# Beetech_Metro_Shield_1_1.net
KiCad netlist of a schematic drawn in Altium Designer
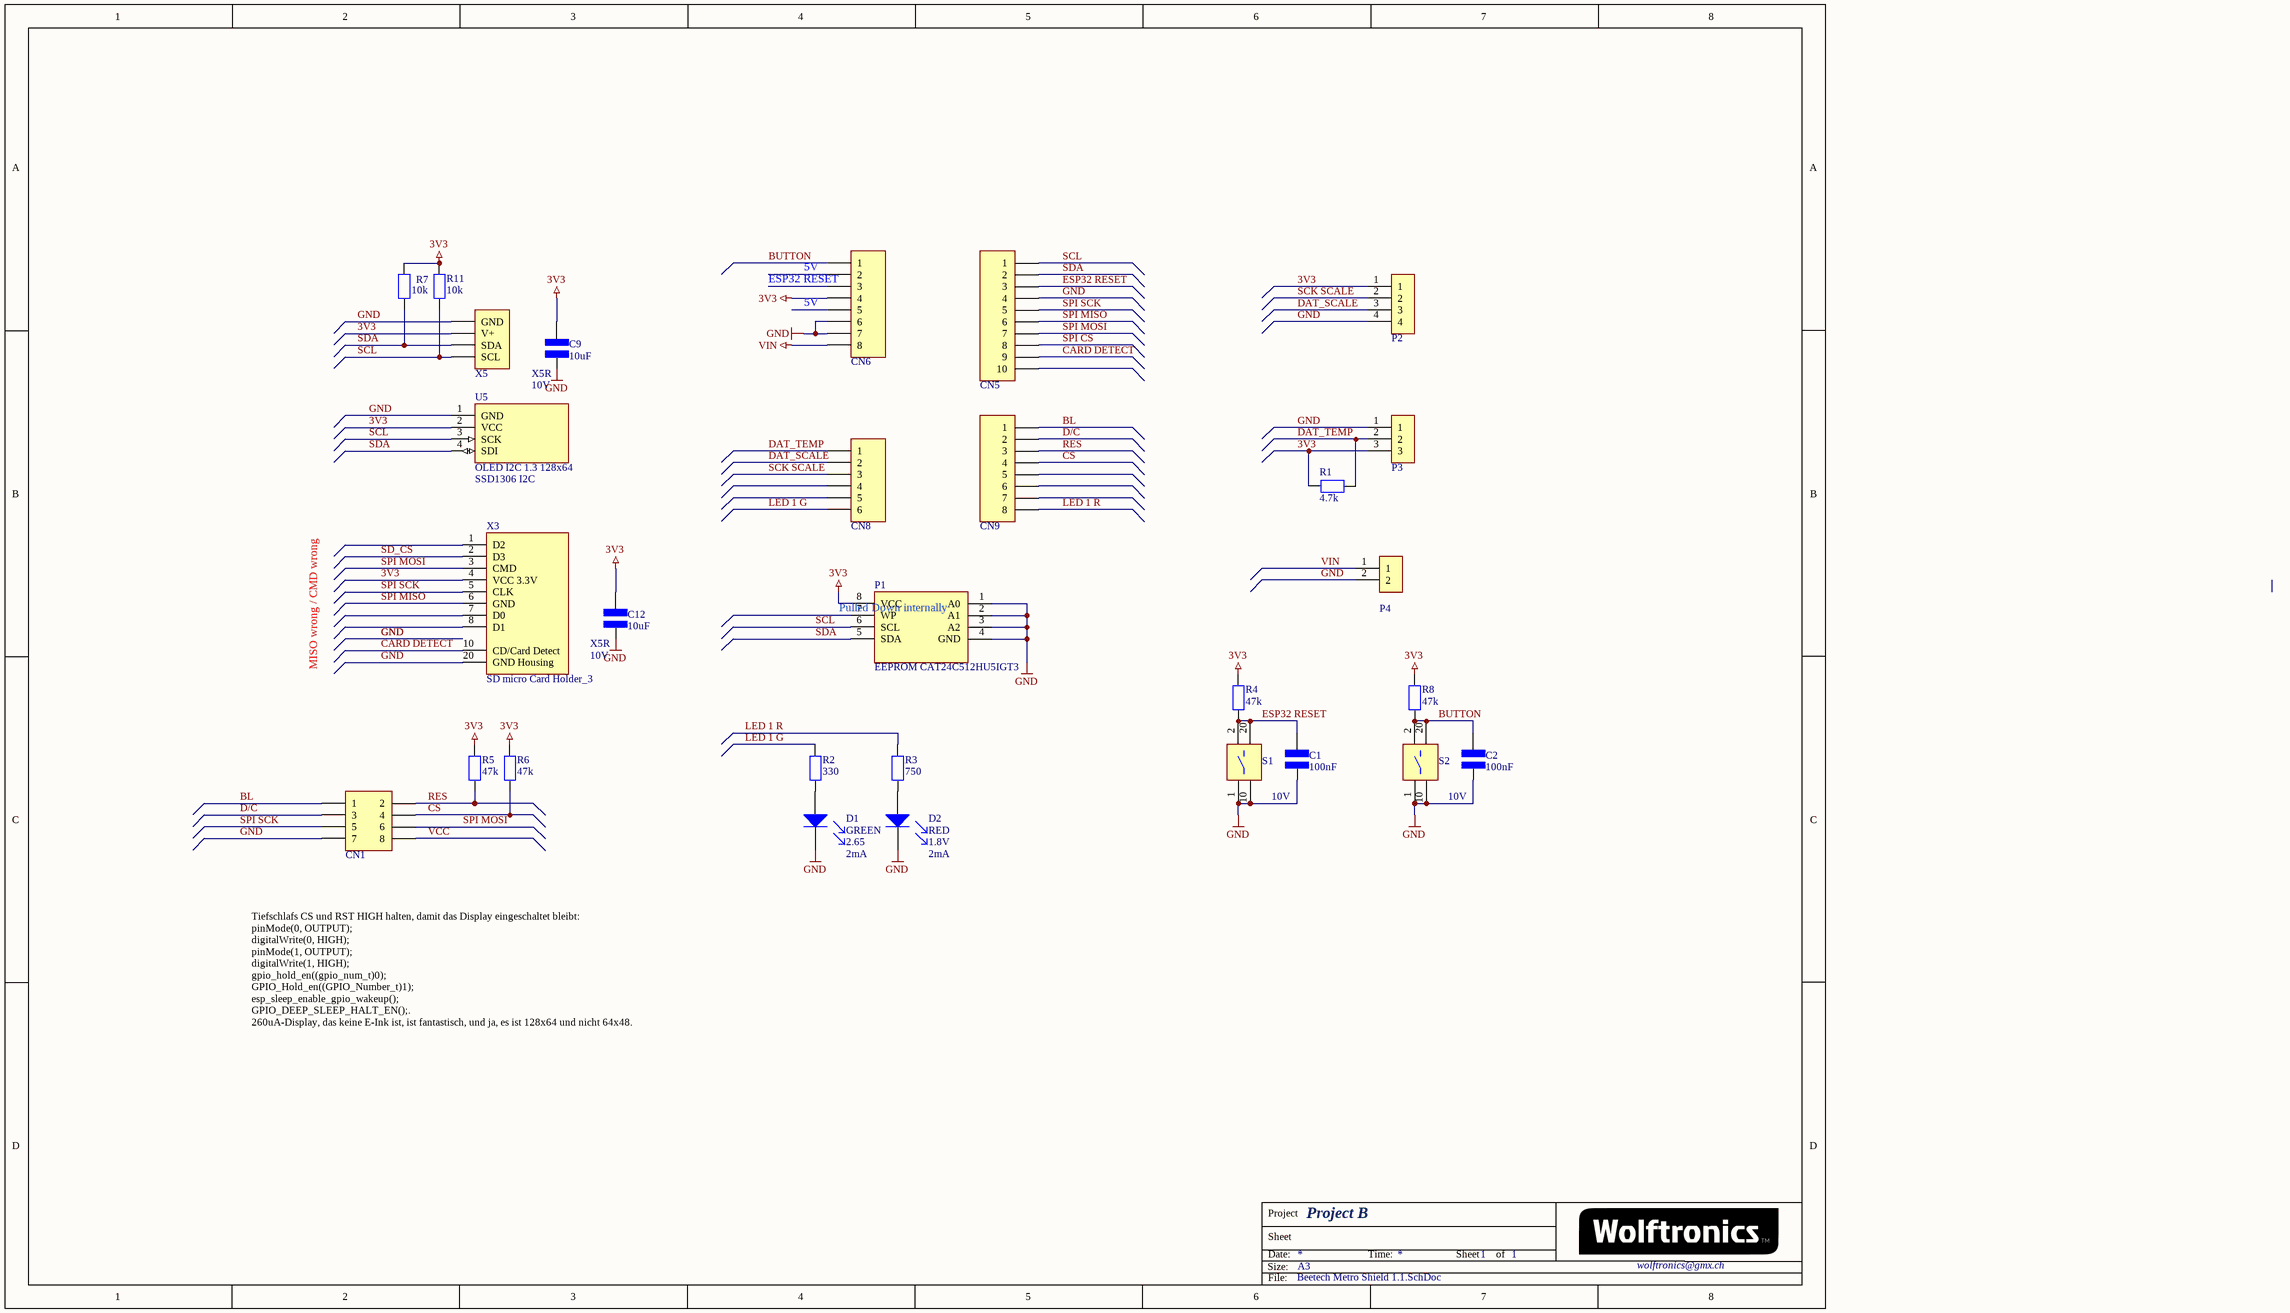
[diagram p0: Beetech Metro Shield 1.1.SchDoc]

(export (version "E")
  (design (tool "Eeschema 10.0.6"))
  (components
    (comp (ref "C1")
      (value "100nF")
      (footprint "CAP 0603 - OUTLINE")
      (description "C CERAMIC SMD")
      (fields (field (name "UMAX") "10V") (field (name "Comment") "100nF 0603"))
      (libsource (lib "Library CAP") (part "100nF 0603"))
    )
    (comp (ref "C2")
      (value "100nF")
      (footprint "CAP 0603 - OUTLINE")
      (description "C CERAMIC SMD")
      (fields (field (name "UMAX") "10V") (field (name "Comment") "100nF 0603"))
      (libsource (lib "Library CAP") (part "100nF 0603"))
    )
    (comp (ref "C9")
      (value "10uF")
      (footprint "CAP 0603 - OUTLINE")
      (description "C CERAMIC SMD")
      (fields
        (field (name "UMAX") "10V")
        (field (name "DIELEKTRIKUM") "X5R")
        (field (name "Comment") "10uF 0603")
      )
      (libsource (lib "Library CAP") (part "10uF 0603"))
    )
    (comp (ref "C12")
      (value "10uF")
      (footprint "CAP 0603 - OUTLINE")
      (description "C CERAMIC SMD")
      (fields
        (field (name "UMAX") "10V")
        (field (name "DIELEKTRIKUM") "X5R")
        (field (name "Comment") "10uF 0603")
      )
      (libsource (lib "Library CAP") (part "10uF 0603"))
    )
    (comp (ref "CN1")
      (value "4 X 2  Header")
      (footprint "4 x 2 2.54mm - no Connector")
      (libsource (lib "Library Scematic") (part "4 X 2  Header"))
    )
    (comp (ref "CN5")
      (value "10-Pin Stiftleiste 10x1 2.54 Low Profile")
      (footprint "10PIN - III")
      (description "Low Profile 10-Pin Stiftleiste 10x1 2.54 Low Profile")
      (libsource (lib "Library Scematic") (part "10-Pin Stiftleiste 10x1 2.54 Low Profile"))
    )
    (comp (ref "CN6")
      (value "8-Pin Stiftleiste 8x1 2.54 Low Profile")
      (footprint "8 PIN - Stiftleiste")
      (description "Low Profile 8-Pin Stiftleiste 8x1 2.54")
      (libsource (lib "") (part "8-Pin Stiftleiste 8x1 2.54 Low Profile_1"))
    )
    (comp (ref "CN8")
      (value "6-PiN")
      (footprint "6PIN")
      (description "6-Pin")
      (fields (field (name "PUBLISHER") "Altium Limited"))
      (libsource (lib "Library Scematic") (part "6-PiN"))
    )
    (comp (ref "CN9")
      (value "8-Pin Stiftleiste 8x1 2.54 Low Profile")
      (footprint "8 PIN - Stiftleiste")
      (description "Low Profile 8-Pin Stiftleiste 8x1 2.54")
      (libsource (lib "Library Scematic") (part "8-Pin Stiftleiste 8x1 2.54 Low Profile"))
    )
    (comp (ref "D1")
      (value "LED Diode SMD LOW CURRENT")
      (footprint "LED SMD 0603 FOOTPRINT")
      (description "LED Green APT1608LZGCK")
      (fields
        (field (name "COLOR") "GREEN")
        (field (name "FORWARD VOLTAGE") "2.65")
        (field (name "IF") "2mA")
      )
      (libsource (lib "Library DIODE") (part "LED Diode SMD - GREEN - 0603 - 2mA_1"))
    )
    (comp (ref "D2")
      (value "LED Diode SMD LOW CURRENT")
      (footprint "LED SMD 0603 FOOTPRINT")
      (description "LED Red APT1608LSECKJ3RV")
      (fields (field (name "COLOR") "RED") (field (name "FORWARD VOLTAGE") "1.8V") (field (name "IF") "2mA"))
      (libsource (lib "Library DIODE") (part "LED Diode SMD - RED - 0603 - 2mA_1"))
    )
    (comp (ref "P1")
      (value "EEPROM CAT24C512HU5IGT3")
      (footprint "UDFN8 3.0x2.0 CAT24C512HU5IGT3")
      (libsource (lib "Library Scematic") (part "EEPROM CAT24C512HU5IGT3"))
    )
    (comp (ref "P2")
      (value "4-Pin Right Angle Housing")
      (footprint "4PIN - RND 205-EK254-2.54-04P")
      (description "4-Pin")
      (libsource (lib "Library Scematic") (part "4-Pin Screw Terminal"))
    )
    (comp (ref "P3")
      (value "3-Pin Right Angle Housing")
      (footprint "3PIN - RND 205-EK254-2.54-03P")
      (description "3-Pin")
      (libsource (lib "Library Scematic") (part "3-Pin Screw Terminal"))
    )
    (comp (ref "P4")
      (value "2-Pin Right Angle Housing")
      (footprint "2PIN - RND 205-EK254-2.54-02P")
      (description "2-Pin")
      (libsource (lib "Library Scematic") (part "2-Pin Screw Terminal"))
    )
    (comp (ref "R1")
      (value "4.7k")
      (footprint "RES 0603 FOOTPRINT - OUTLINE")
      (description "R SMD")
      (fields (field (name "Comment") "4.7k Ohm 0603"))
      (libsource (lib "Library RES") (part "4.7k Ohm 0603"))
    )
    (comp (ref "R2")
      (value "330")
      (footprint "RES 0603 FOOTPRINT - OUTLINE")
      (description "R SMD")
      (fields (field (name "Comment") "330 Ohm 0603"))
      (libsource (lib "Library RES") (part "330 Ohm 0603"))
    )
    (comp (ref "R3")
      (value "750")
      (footprint "RES 0603 FOOTPRINT - OUTLINE")
      (description "R SMD")
      (fields (field (name "Comment") "750 Ohm 0603"))
      (libsource (lib "Library RES") (part "750 Ohm 0603"))
    )
    (comp (ref "R4")
      (value "47k")
      (footprint "RES 0603 FOOTPRINT - OUTLINE")
      (description "R SMD")
      (fields (field (name "Comment") "47k Ohm 0603"))
      (libsource (lib "Library RES") (part "47k Ohm 0603"))
    )
    (comp (ref "R5")
      (value "47k")
      (footprint "RES 0603 FOOTPRINT - OUTLINE")
      (description "R SMD")
      (fields (field (name "Comment") "47k Ohm 0603"))
      (libsource (lib "Library RES") (part "47k Ohm 0603"))
    )
    (comp (ref "R6")
      (value "47k")
      (footprint "RES 0603 FOOTPRINT - OUTLINE")
      (description "R SMD")
      (fields (field (name "Comment") "47k Ohm 0603"))
      (libsource (lib "Library RES") (part "47k Ohm 0603"))
    )
    (comp (ref "R7")
      (value "10k")
      (footprint "RES 0603 FOOTPRINT - OUTLINE")
      (description "R SMD")
      (fields (field (name "Comment") "10k Ohm 0603"))
      (libsource (lib "Library RES") (part "10k Ohm 0603"))
    )
    (comp (ref "R8")
      (value "47k")
      (footprint "RES 0603 FOOTPRINT - OUTLINE")
      (description "R SMD")
      (fields (field (name "Comment") "47k Ohm 0603"))
      (libsource (lib "Library RES") (part "47k Ohm 0603"))
    )
    (comp (ref "R11")
      (value "10k")
      (footprint "RES 0603 FOOTPRINT - OUTLINE")
      (description "R SMD")
      (fields (field (name "Comment") "10k Ohm 0603"))
      (libsource (lib "Library RES") (part "10k Ohm 0603"))
    )
    (comp (ref "S1")
      (value "Taster Print_SMD_2")
      (footprint "Taster Print - SMD - KMR241G LFS")
      (description "Taster")
      (libsource (lib "Library Scematic") (part "Taster Print_SMD_2"))
    )
    (comp (ref "S2")
      (value "Taster Print_SMD_2")
      (footprint "Taster Print - SMD - KMR241G LFS")
      (description "Taster")
      (libsource (lib "Library Scematic") (part "Taster Print_SMD_2"))
    )
    (comp (ref "U5")
      (value "OLED I2C 1.3 128x64")
      (footprint "OLED 1.3 128x64 I2C")
      (description "SSD1306 I2C")
      (fields (field (name "CHIP") "SSD1306 I2C"))
      (libsource (lib "Library Scematic") (part "OLED I2C 1.3 128x64"))
    )
    (comp (ref "X3")
      (value "SD micro Card Holder_3")
      (footprint "SD Card Holder - micro - 3 - sd Card inserted")
      (description "SD micro Card  Holder")
      (libsource (lib "Library Scematic") (part "SD micro Card Holder_3"))
    )
    (comp (ref "X5")
      (value "4-Pin")
      (footprint "QWIIC JST CONNECTOR - SMD 4-PIN")
      (description "QWIIC JST CONNECTOR - SMD 4-PIN")
      (libsource (lib "Library Scematic") (part "4-Pin QWIIC JST CONNECTOR - SMD 4_1"))
    )
  )
  (nets
    (net (code "1") (name "/BL") (class "Default")
      (node (ref "CN1") (pin "1") (pinfunction "1_1") (pintype "passive"))
      (node (ref "CN9") (pin "1") (pinfunction "1_1") (pintype "passive"))
    )
    (net (code "2") (name "/BUTTON") (class "Default")
      (node (ref "C2") (pin "2") (pinfunction "2_2") (pintype "passive"))
      (node (ref "CN6") (pin "1") (pinfunction "1_1") (pintype "passive"))
      (node (ref "R8") (pin "2") (pinfunction "2_2") (pintype "passive"))
      (node (ref "S2") (pin "2") (pinfunction "2_2") (pintype "passive"))
      (node (ref "S2") (pin "20") (pinfunction "20_20") (pintype "passive"))
    )
    (net (code "3") (name "/CARD DETECT") (class "Default")
      (node (ref "CN5") (pin "9") (pinfunction "9_9") (pintype "passive"))
      (node (ref "X3") (pin "10") (pinfunction "CD/Card_Detect_10") (pintype "passive"))
    )
    (net (code "4") (name "/CS") (class "Default")
      (node (ref "CN1") (pin "4") (pinfunction "4_4") (pintype "passive"))
      (node (ref "CN9") (pin "4") (pinfunction "4_4") (pintype "passive"))
      (node (ref "R6") (pin "1") (pinfunction "1_1") (pintype "passive"))
    )
    (net (code "5") (name "/DAT_SCALE") (class "Default")
      (node (ref "CN8") (pin "2") (pinfunction "2_2") (pintype "passive"))
      (node (ref "P2") (pin "3") (pinfunction "3_3") (pintype "passive"))
    )
    (net (code "6") (name "/DAT_TEMP") (class "Default")
      (node (ref "CN8") (pin "1") (pinfunction "1_1") (pintype "passive"))
      (node (ref "P3") (pin "2") (pinfunction "2_2") (pintype "passive"))
      (node (ref "R1") (pin "1") (pinfunction "1_1") (pintype "passive"))
    )
    (net (code "7") (name "/D{slash}C") (class "Default")
      (node (ref "CN1") (pin "3") (pinfunction "3_3") (pintype "passive"))
      (node (ref "CN9") (pin "2") (pinfunction "2_2") (pintype "passive"))
    )
    (net (code "8") (name "/ESP32 RESET") (class "Default")
      (node (ref "C1") (pin "2") (pinfunction "2_2") (pintype "passive"))
      (node (ref "CN5") (pin "3") (pinfunction "3_3") (pintype "passive"))
      (node (ref "R4") (pin "2") (pinfunction "2_2") (pintype "passive"))
      (node (ref "S1") (pin "2") (pinfunction "2_2") (pintype "passive"))
      (node (ref "S1") (pin "20") (pinfunction "20_20") (pintype "passive"))
    )
    (net (code "9") (name "/LED 1 G") (class "Default")
      (node (ref "CN8") (pin "6") (pinfunction "6_6") (pintype "passive"))
      (node (ref "R2") (pin "2") (pinfunction "2_2") (pintype "passive"))
    )
    (net (code "10") (name "/LED 1 R") (class "Default")
      (node (ref "CN9") (pin "8") (pinfunction "8_8") (pintype "passive"))
      (node (ref "R3") (pin "2") (pinfunction "2_2") (pintype "passive"))
    )
    (net (code "11") (name "/RES") (class "Default")
      (node (ref "CN1") (pin "2") (pinfunction "2_2") (pintype "passive"))
      (node (ref "CN9") (pin "3") (pinfunction "3_3") (pintype "passive"))
      (node (ref "R5") (pin "1") (pinfunction "1_1") (pintype "passive"))
    )
    (net (code "12") (name "/SCK SCALE") (class "Default")
      (node (ref "CN8") (pin "3") (pinfunction "3_3") (pintype "passive"))
      (node (ref "P2") (pin "2") (pinfunction "2_2") (pintype "passive"))
    )
    (net (code "13") (name "/SCL") (class "Default")
      (node (ref "CN5") (pin "1") (pinfunction "1_1") (pintype "passive"))
      (node (ref "P1") (pin "6") (pinfunction "SCL_6") (pintype "passive"))
      (node (ref "R11") (pin "1") (pinfunction "1_1") (pintype "passive"))
      (node (ref "U5") (pin "3") (pinfunction "SCK_3") (pintype "input"))
      (node (ref "X5") (pin "1") (pinfunction "SCL_1") (pintype "passive"))
    )
    (net (code "14") (name "/SDA") (class "Default")
      (node (ref "CN5") (pin "2") (pinfunction "2_2") (pintype "passive"))
      (node (ref "P1") (pin "5") (pinfunction "SDA_5") (pintype "passive"))
      (node (ref "R7") (pin "1") (pinfunction "1_1") (pintype "passive"))
      (node (ref "U5") (pin "4") (pinfunction "SDI_4") (pintype "bidirectional"))
      (node (ref "X5") (pin "2") (pinfunction "SDA_2") (pintype "passive"))
    )
    (net (code "15") (name "/SD_CS") (class "Default")
      (node (ref "X3") (pin "2") (pinfunction "D3_2") (pintype "passive"))
    )
    (net (code "16") (name "/SPI CS") (class "Default")
      (node (ref "CN5") (pin "8") (pinfunction "8_8") (pintype "passive"))
    )
    (net (code "17") (name "/SPI MISO") (class "Default")
      (node (ref "CN5") (pin "6") (pinfunction "6_6") (pintype "passive"))
      (node (ref "X3") (pin "6") (pinfunction "GND_6") (pintype "passive"))
    )
    (net (code "18") (name "/SPI MOSI") (class "Default")
      (node (ref "CN1") (pin "6") (pinfunction "6_6") (pintype "passive"))
      (node (ref "CN5") (pin "7") (pinfunction "7_7") (pintype "passive"))
      (node (ref "X3") (pin "3") (pinfunction "CMD_3") (pintype "passive"))
    )
    (net (code "19") (name "/SPI SCK") (class "Default")
      (node (ref "CN1") (pin "5") (pinfunction "5_5") (pintype "passive"))
      (node (ref "CN5") (pin "5") (pinfunction "5_5") (pintype "passive"))
      (node (ref "X3") (pin "5") (pinfunction "CLK_5") (pintype "passive"))
    )
    (net (code "20") (name "/VCC") (class "Default")
      (node (ref "CN1") (pin "8") (pinfunction "8_8") (pintype "passive"))
    )
    (net (code "21") (name "3V3") (class "Default")
      (node (ref "C12") (pin "2") (pinfunction "2_2") (pintype "passive"))
      (node (ref "C9") (pin "2") (pinfunction "2_2") (pintype "passive"))
      (node (ref "CN6") (pin "4") (pinfunction "4_4") (pintype "passive"))
      (node (ref "P1") (pin "8") (pinfunction "VCC_8") (pintype "passive"))
      (node (ref "P2") (pin "1") (pinfunction "1_1") (pintype "passive"))
      (node (ref "P3") (pin "3") (pinfunction "3_3") (pintype "passive"))
      (node (ref "R1") (pin "2") (pinfunction "2_2") (pintype "passive"))
      (node (ref "R11") (pin "2") (pinfunction "2_2") (pintype "passive"))
      (node (ref "R4") (pin "1") (pinfunction "1_1") (pintype "passive"))
      (node (ref "R5") (pin "2") (pinfunction "2_2") (pintype "passive"))
      (node (ref "R6") (pin "2") (pinfunction "2_2") (pintype "passive"))
      (node (ref "R7") (pin "2") (pinfunction "2_2") (pintype "passive"))
      (node (ref "R8") (pin "1") (pinfunction "1_1") (pintype "passive"))
      (node (ref "U5") (pin "2") (pinfunction "VCC_2") (pintype "power_in"))
      (node (ref "X3") (pin "4") (pinfunction "VCC_3.3V_4") (pintype "passive"))
      (node (ref "X5") (pin "3") (pinfunction "V+_3") (pintype "passive"))
    )
    (net (code "22") (name "GND") (class "Default")
      (node (ref "C1") (pin "1") (pinfunction "1_1") (pintype "passive"))
      (node (ref "C12") (pin "1") (pinfunction "1_1") (pintype "passive"))
      (node (ref "C2") (pin "1") (pinfunction "1_1") (pintype "passive"))
      (node (ref "C9") (pin "1") (pinfunction "1_1") (pintype "passive"))
      (node (ref "CN1") (pin "7") (pinfunction "7_7") (pintype "passive"))
      (node (ref "CN5") (pin "4") (pinfunction "4_4") (pintype "passive"))
      (node (ref "CN6") (pin "6") (pinfunction "6_6") (pintype "passive"))
      (node (ref "CN6") (pin "7") (pinfunction "7_7") (pintype "passive"))
      (node (ref "D1") (pin "2") (pinfunction "K_2") (pintype "passive"))
      (node (ref "D2") (pin "2") (pinfunction "K_2") (pintype "passive"))
      (node (ref "P1") (pin "1") (pinfunction "A0_1") (pintype "passive"))
      (node (ref "P1") (pin "2") (pinfunction "A1_2") (pintype "passive"))
      (node (ref "P1") (pin "3") (pinfunction "A2_3") (pintype "passive"))
      (node (ref "P1") (pin "4") (pinfunction "GND_4") (pintype "passive"))
      (node (ref "P2") (pin "4") (pinfunction "4_4") (pintype "passive"))
      (node (ref "P3") (pin "1") (pinfunction "1_1") (pintype "passive"))
      (node (ref "P4") (pin "2") (pinfunction "2_2") (pintype "passive"))
      (node (ref "S1") (pin "1") (pinfunction "1_1") (pintype "passive"))
      (node (ref "S1") (pin "10") (pinfunction "10_10") (pintype "passive"))
      (node (ref "S2") (pin "1") (pinfunction "1_1") (pintype "passive"))
      (node (ref "S2") (pin "10") (pinfunction "10_10") (pintype "passive"))
      (node (ref "U5") (pin "1") (pinfunction "GND_1") (pintype "power_in"))
      (node (ref "X3") (pin "20") (pinfunction "GND_Housing_20") (pintype "passive"))
      (node (ref "X5") (pin "4") (pinfunction "GND_4") (pintype "passive"))
    )
    (net (code "23") (name "Net-(D1-A)") (class "Default")
      (node (ref "D1") (pin "1") (pinfunction "A_1") (pintype "passive"))
      (node (ref "R2") (pin "1") (pinfunction "1_1") (pintype "passive"))
    )
    (net (code "24") (name "Net-(D2-A)") (class "Default")
      (node (ref "D2") (pin "1") (pinfunction "A_1") (pintype "passive"))
      (node (ref "R3") (pin "1") (pinfunction "1_1") (pintype "passive"))
    )
    (net (code "25") (name "VIN") (class "Default")
      (node (ref "CN6") (pin "8") (pinfunction "8_8") (pintype "passive"))
      (node (ref "P4") (pin "1") (pinfunction "1_1") (pintype "passive"))
    )
    (net (code "26") (name "unconnected-(CN5-Pad10)") (class "Default")
      (node (ref "CN5") (pin "10") (pinfunction "10_10") (pintype "passive"))
    )
    (net (code "27") (name "unconnected-(CN6-Pad2)") (class "Default")
      (node (ref "CN6") (pin "2") (pinfunction "2_2") (pintype "passive"))
    )
    (net (code "28") (name "unconnected-(CN6-Pad3)") (class "Default")
      (node (ref "CN6") (pin "3") (pinfunction "3_3") (pintype "passive"))
    )
    (net (code "29") (name "unconnected-(CN6-Pad5)") (class "Default")
      (node (ref "CN6") (pin "5") (pinfunction "5_5") (pintype "passive"))
    )
    (net (code "30") (name "unconnected-(CN8-Pad4)") (class "Default")
      (node (ref "CN8") (pin "4") (pinfunction "4_4") (pintype "passive"))
    )
    (net (code "31") (name "unconnected-(CN8-Pad5)") (class "Default")
      (node (ref "CN8") (pin "5") (pinfunction "5_5") (pintype "passive"))
    )
    (net (code "32") (name "unconnected-(CN9-Pad5)") (class "Default")
      (node (ref "CN9") (pin "5") (pinfunction "5_5") (pintype "passive"))
    )
    (net (code "33") (name "unconnected-(CN9-Pad6)") (class "Default")
      (node (ref "CN9") (pin "6") (pinfunction "6_6") (pintype "passive"))
    )
    (net (code "34") (name "unconnected-(CN9-Pad7)") (class "Default")
      (node (ref "CN9") (pin "7") (pinfunction "7_7") (pintype "passive"))
    )
    (net (code "35") (name "unconnected-(P1-WP-Pad7)") (class "Default")
      (node (ref "P1") (pin "7") (pinfunction "WP_7") (pintype "passive"))
    )
    (net (code "36") (name "unconnected-(X3-D0-Pad7)") (class "Default")
      (node (ref "X3") (pin "7") (pinfunction "D0_7") (pintype "passive"))
    )
    (net (code "37") (name "unconnected-(X3-D1-Pad8)") (class "Default")
      (node (ref "X3") (pin "8") (pinfunction "D1_8") (pintype "passive"))
    )
    (net (code "38") (name "unconnected-(X3-D2-Pad1)") (class "Default")
      (node (ref "X3") (pin "1") (pinfunction "D2_1") (pintype "passive"))
    )
  )
)
